# SCH_Decimal_Display_2021-10-08.net
KiCad netlist of a schematic drawn in EasyEDA
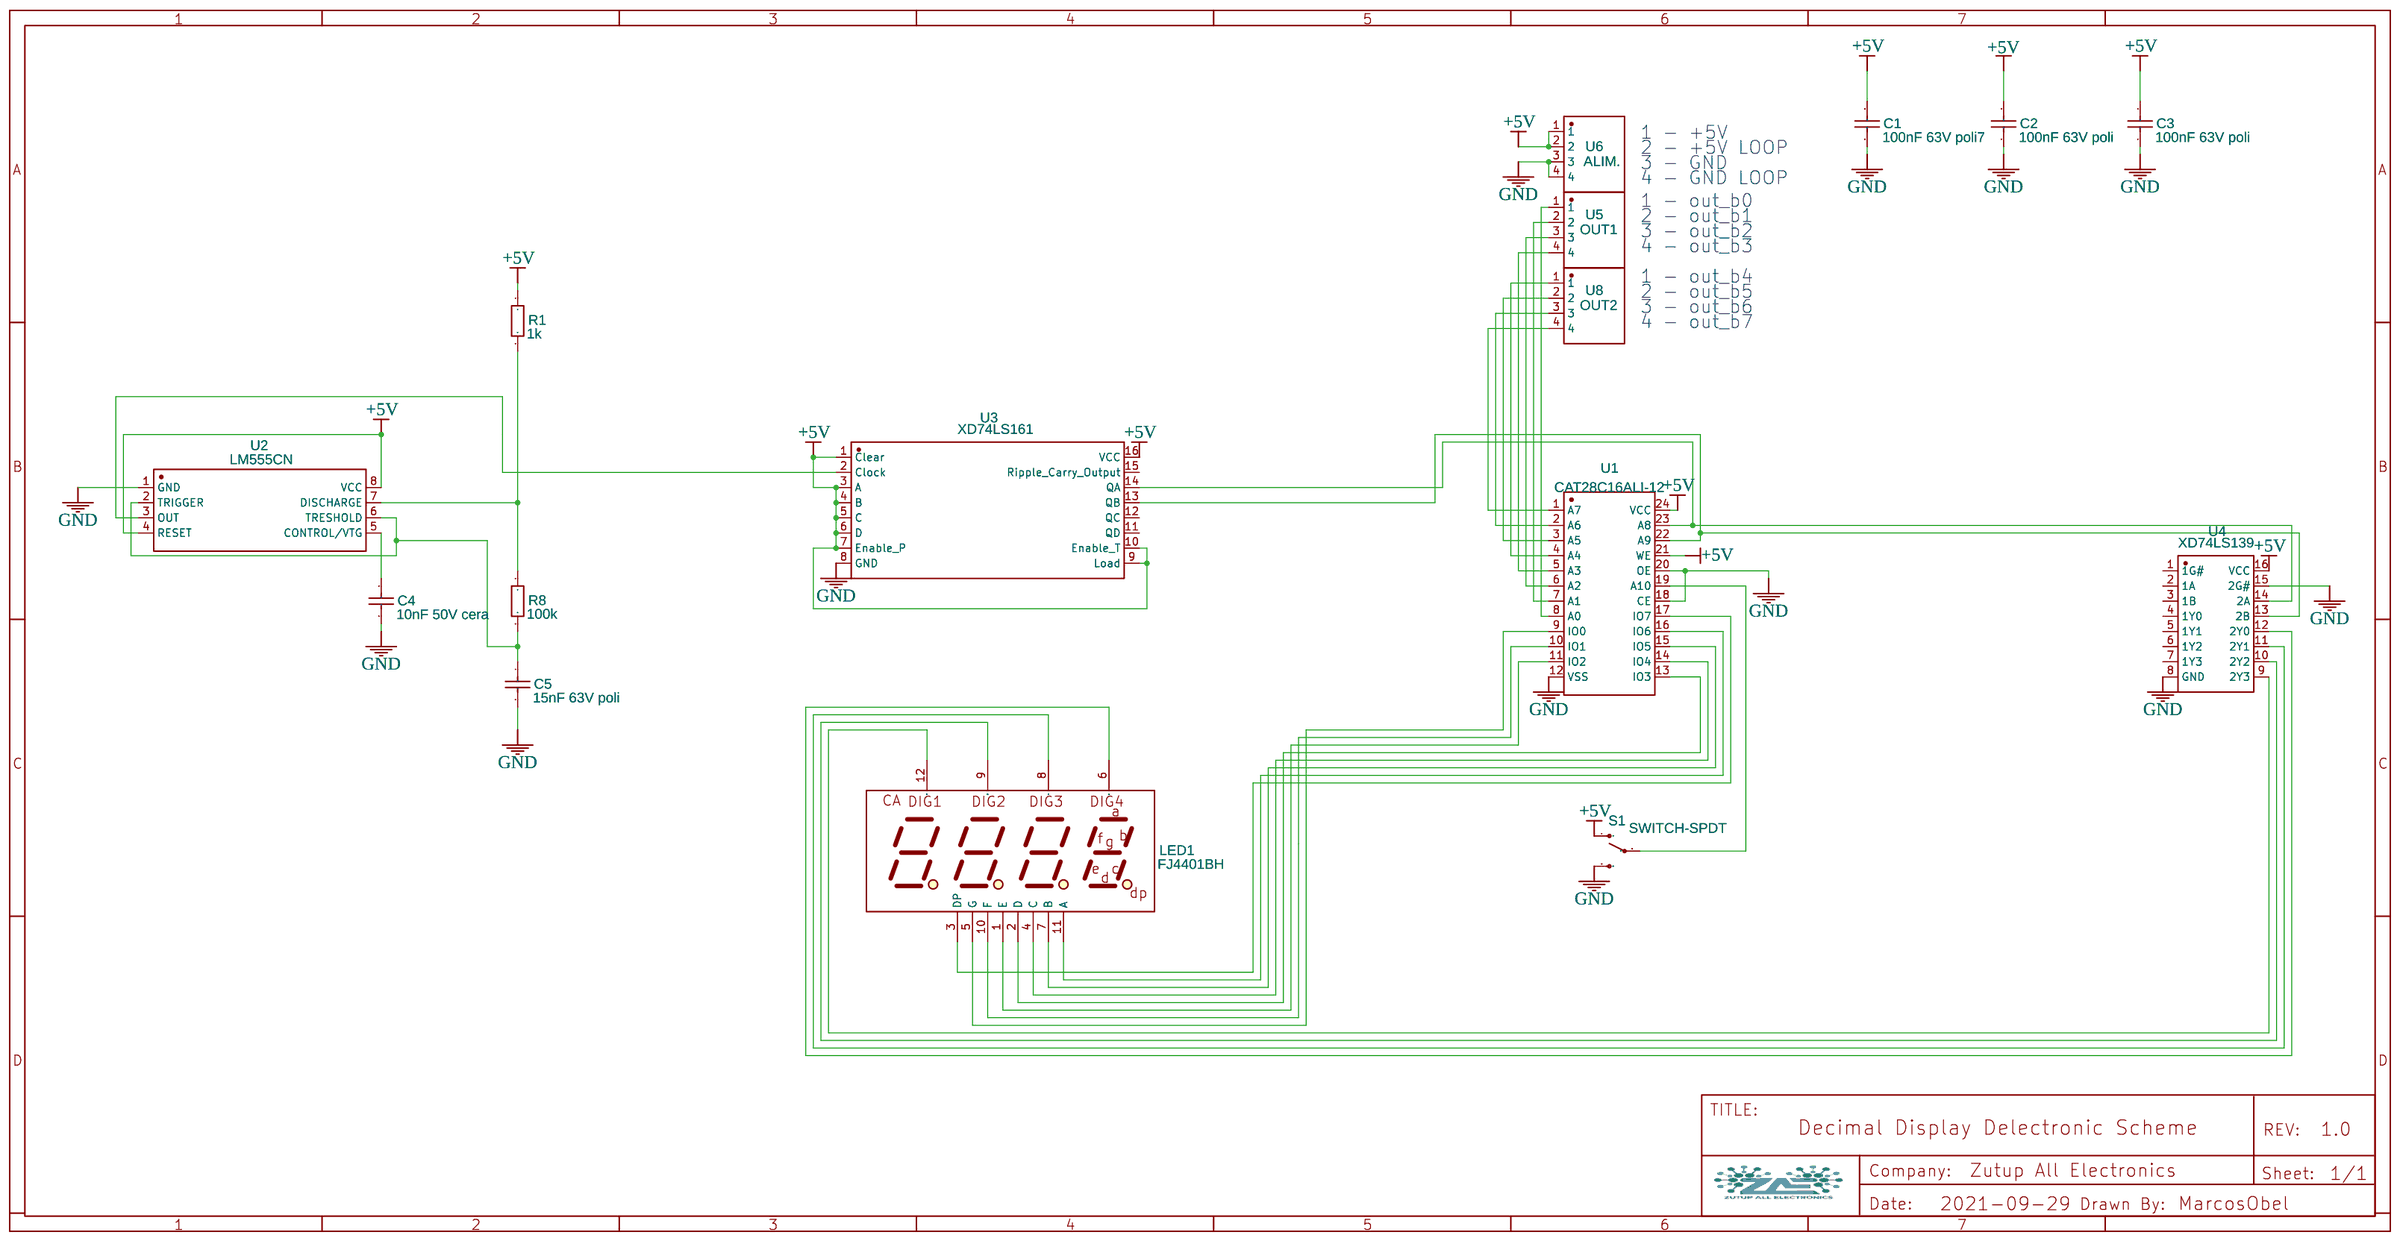
[diagram p0: schematic sheet]

(export (version "E")
  (design (tool "Eeschema 10.0.6"))
  (components
    (comp (ref "C1")
      (value "100nF 63V poli7")
      (fields
        (field (name "BOM_Manufacturer Part") "SR305C105KAR")
        (field (name "BOM_Supplier Part") "C444741")
      )
      (libsource (lib "") (part "SR305C105KAR"))
    )
    (comp (ref "C2")
      (value "100nF 63V poli")
      (fields
        (field (name "BOM_Manufacturer Part") "SR305C105KAR")
        (field (name "BOM_Supplier Part") "C444741")
      )
      (libsource (lib "") (part "SR305C105KAR"))
    )
    (comp (ref "C3")
      (value "100nF 63V poli")
      (fields
        (field (name "BOM_Manufacturer Part") "SR305C105KAR")
        (field (name "BOM_Supplier Part") "C444741")
      )
      (libsource (lib "") (part "SR305C105KAR"))
    )
    (comp (ref "C4")
      (value "10nF 50V cera")
      (fields
        (field (name "BOM_Manufacturer Part") "SR305C105KAR")
        (field (name "BOM_Supplier Part") "C444741")
      )
      (libsource (lib "") (part "SR305C105KAR"))
    )
    (comp (ref "C5")
      (value "15nF 63V poli")
      (fields
        (field (name "BOM_Manufacturer Part") "SR305C105KAR")
        (field (name "BOM_Supplier Part") "C444741")
      )
      (libsource (lib "") (part "SR305C105KAR"))
    )
    (comp (ref "LED1")
      (value "FJ4401BH")
      (fields (field (name "BOM_Supplier Part") "C10712"))
      (libsource (lib "") (part "FJ4401BH"))
    )
    (comp (ref "R1")
      (value "1k")
      (fields
        (field (name "BOM_Manufacturer Part") "CFR02SJ0823A10")
        (field (name "BOM_Supplier Part") "C69876")
      )
      (libsource (lib "") (part "CFR02SJ0823A10"))
    )
    (comp (ref "R8")
      (value "100k")
      (fields
        (field (name "BOM_Manufacturer Part") "CFR02SJ0823A10")
        (field (name "BOM_Supplier Part") "C69876")
      )
      (libsource (lib "") (part "CFR02SJ0823A10"))
    )
    (comp (ref "S1") (value "SWITCH-SPDT") (libsource (lib "") (part "SWITCH-SPDT")))
    (comp (ref "U1") (value "CAT28C16ALI-12") (libsource (lib "") (part "CAT28C16ALI-12")))
    (comp (ref "U2")
      (value "LM555CN")
      (fields (field (name "BOM_Supplier Part") "C110322"))
      (libsource (lib "") (part "LM555CN"))
    )
    (comp (ref "U3")
      (value "XD74LS161")
      (fields (field (name "BOM_Supplier Part") "C609766"))
      (libsource (lib "") (part "XD74LS161"))
    )
    (comp (ref "U4")
      (value "XD74LS139")
      (fields (field (name "BOM_Supplier Part") "C521175"))
      (libsource (lib "") (part "XD74LS139"))
    )
    (comp (ref "U5")
      (value "OUT1")
      (fields (field (name "BOM_Manufacturer Part") "171825-4") (field (name "BOM_Supplier Part") "C210162"))
      (libsource (lib "") (part "171825-4"))
    )
    (comp (ref "U6")
      (value "ALIM.")
      (fields (field (name "BOM_Manufacturer Part") "171825-4") (field (name "BOM_Supplier Part") "C210162"))
      (libsource (lib "") (part "171825-4"))
    )
    (comp (ref "U8")
      (value "OUT2")
      (fields (field (name "BOM_Manufacturer Part") "171825-4") (field (name "BOM_Supplier Part") "C210162"))
      (libsource (lib "") (part "171825-4"))
    )
  )
  (nets
    (net (code "1") (name "+5V") (class "Default")
      (node (ref "C1") (pin "1") (pinfunction "1_1") (pintype "input"))
      (node (ref "C2") (pin "1") (pinfunction "1_1") (pintype "input"))
      (node (ref "C3") (pin "1") (pinfunction "1_1") (pintype "input"))
      (node (ref "R1") (pin "1") (pinfunction "1_1") (pintype "input"))
      (node (ref "S1") (pin "1") (pinfunction "O_1") (pintype "unspecified"))
      (node (ref "U1") (pin "21") (pinfunction "WE_21") (pintype "unspecified"))
      (node (ref "U1") (pin "24") (pinfunction "VCC_24") (pintype "unspecified"))
      (node (ref "U2") (pin "4") (pinfunction "RESET_4") (pintype "unspecified"))
      (node (ref "U2") (pin "8") (pinfunction "VCC_8") (pintype "unspecified"))
      (node (ref "U3") (pin "1") (pinfunction "Clear_1") (pintype "unspecified"))
      (node (ref "U3") (pin "10") (pinfunction "Enable_T_10") (pintype "unspecified"))
      (node (ref "U3") (pin "16") (pinfunction "VCC_16") (pintype "unspecified"))
      (node (ref "U3") (pin "3") (pinfunction "A_3") (pintype "unspecified"))
      (node (ref "U3") (pin "4") (pinfunction "B_4") (pintype "unspecified"))
      (node (ref "U3") (pin "5") (pinfunction "C_5") (pintype "unspecified"))
      (node (ref "U3") (pin "6") (pinfunction "D_6") (pintype "unspecified"))
      (node (ref "U3") (pin "7") (pinfunction "Enable_P_7") (pintype "unspecified"))
      (node (ref "U3") (pin "9") (pinfunction "Load_9") (pintype "unspecified"))
      (node (ref "U4") (pin "16") (pinfunction "VCC_16") (pintype "unspecified"))
      (node (ref "U6") (pin "1") (pinfunction "1_1") (pintype "unspecified"))
      (node (ref "U6") (pin "2") (pinfunction "2_2") (pintype "unspecified"))
    )
    (net (code "2") (name "GND") (class "Default")
      (node (ref "C1") (pin "2") (pinfunction "2_2") (pintype "input"))
      (node (ref "C2") (pin "2") (pinfunction "2_2") (pintype "input"))
      (node (ref "C3") (pin "2") (pinfunction "2_2") (pintype "input"))
      (node (ref "C4") (pin "2") (pinfunction "2_2") (pintype "input"))
      (node (ref "C5") (pin "2") (pinfunction "2_2") (pintype "input"))
      (node (ref "S1") (pin "3") (pinfunction "S_3") (pintype "unspecified"))
      (node (ref "U1") (pin "12") (pinfunction "VSS_12") (pintype "unspecified"))
      (node (ref "U1") (pin "18") (pinfunction "CE_18") (pintype "unspecified"))
      (node (ref "U1") (pin "20") (pinfunction "OE_20") (pintype "unspecified"))
      (node (ref "U2") (pin "1") (pinfunction "GND_1") (pintype "unspecified"))
      (node (ref "U3") (pin "8") (pinfunction "GND_8") (pintype "unspecified"))
      (node (ref "U4") (pin "15") (pinfunction "2G#_15") (pintype "unspecified"))
      (node (ref "U4") (pin "8") (pinfunction "GND_8") (pintype "unspecified"))
      (node (ref "U6") (pin "3") (pinfunction "3_3") (pintype "unspecified"))
      (node (ref "U6") (pin "4") (pinfunction "4_4") (pintype "unspecified"))
    )
    (net (code "3") (name "Net-(LED1-A)") (class "Default")
      (node (ref "LED1") (pin "11") (pinfunction "A_11") (pintype "input"))
      (node (ref "U1") (pin "16") (pinfunction "IO6_16") (pintype "unspecified"))
    )
    (net (code "4") (name "Net-(LED1-B)") (class "Default")
      (node (ref "LED1") (pin "7") (pinfunction "B_7") (pintype "input"))
      (node (ref "U1") (pin "15") (pinfunction "IO5_15") (pintype "unspecified"))
    )
    (net (code "5") (name "Net-(LED1-C)") (class "Default")
      (node (ref "LED1") (pin "4") (pinfunction "C_4") (pintype "input"))
      (node (ref "U1") (pin "14") (pinfunction "IO4_14") (pintype "unspecified"))
    )
    (net (code "6") (name "Net-(LED1-D)") (class "Default")
      (node (ref "LED1") (pin "2") (pinfunction "D_2") (pintype "input"))
      (node (ref "U1") (pin "13") (pinfunction "IO3_13") (pintype "unspecified"))
    )
    (net (code "7") (name "Net-(LED1-DIG1)") (class "Default")
      (node (ref "LED1") (pin "12") (pinfunction "DIG1_12") (pintype "input"))
      (node (ref "U4") (pin "9") (pinfunction "2Y3_9") (pintype "unspecified"))
    )
    (net (code "8") (name "Net-(LED1-DIG2)") (class "Default")
      (node (ref "LED1") (pin "9") (pinfunction "DIG2_9") (pintype "input"))
      (node (ref "U4") (pin "10") (pinfunction "2Y2_10") (pintype "unspecified"))
    )
    (net (code "9") (name "Net-(LED1-DIG3)") (class "Default")
      (node (ref "LED1") (pin "8") (pinfunction "DIG3_8") (pintype "input"))
      (node (ref "U4") (pin "11") (pinfunction "2Y1_11") (pintype "unspecified"))
    )
    (net (code "10") (name "Net-(LED1-DIG4)") (class "Default")
      (node (ref "LED1") (pin "6") (pinfunction "DIG4_6") (pintype "input"))
      (node (ref "U4") (pin "12") (pinfunction "2Y0_12") (pintype "unspecified"))
    )
    (net (code "11") (name "Net-(LED1-DP)") (class "Default")
      (node (ref "LED1") (pin "3") (pinfunction "DP_3") (pintype "input"))
      (node (ref "U1") (pin "17") (pinfunction "IO7_17") (pintype "unspecified"))
    )
    (net (code "12") (name "Net-(LED1-E)") (class "Default")
      (node (ref "LED1") (pin "1") (pinfunction "E_1") (pintype "input"))
      (node (ref "U1") (pin "11") (pinfunction "IO2_11") (pintype "unspecified"))
    )
    (net (code "13") (name "Net-(LED1-F)") (class "Default")
      (node (ref "LED1") (pin "10") (pinfunction "F_10") (pintype "input"))
      (node (ref "U1") (pin "10") (pinfunction "IO1_10") (pintype "unspecified"))
    )
    (net (code "14") (name "Net-(LED1-G)") (class "Default")
      (node (ref "LED1") (pin "5") (pinfunction "G_5") (pintype "input"))
      (node (ref "U1") (pin "9") (pinfunction "IO0_9") (pintype "unspecified"))
    )
    (net (code "15") (name "Net-(S1-P)") (class "Default")
      (node (ref "S1") (pin "2") (pinfunction "P_2") (pintype "unspecified"))
      (node (ref "U1") (pin "19") (pinfunction "A10_19") (pintype "unspecified"))
    )
    (net (code "16") (name "Net-(U1-A0)") (class "Default")
      (node (ref "U1") (pin "8") (pinfunction "A0_8") (pintype "unspecified"))
      (node (ref "U5") (pin "1") (pinfunction "1_1") (pintype "unspecified"))
    )
    (net (code "17") (name "Net-(U1-A1)") (class "Default")
      (node (ref "U1") (pin "7") (pinfunction "A1_7") (pintype "unspecified"))
      (node (ref "U5") (pin "2") (pinfunction "2_2") (pintype "unspecified"))
    )
    (net (code "18") (name "Net-(U1-A2)") (class "Default")
      (node (ref "U1") (pin "6") (pinfunction "A2_6") (pintype "unspecified"))
      (node (ref "U5") (pin "3") (pinfunction "3_3") (pintype "unspecified"))
    )
    (net (code "19") (name "Net-(U1-A3)") (class "Default")
      (node (ref "U1") (pin "5") (pinfunction "A3_5") (pintype "unspecified"))
      (node (ref "U5") (pin "4") (pinfunction "4_4") (pintype "unspecified"))
    )
    (net (code "20") (name "Net-(U1-A4)") (class "Default")
      (node (ref "U1") (pin "4") (pinfunction "A4_4") (pintype "unspecified"))
      (node (ref "U8") (pin "1") (pinfunction "1_1") (pintype "unspecified"))
    )
    (net (code "21") (name "Net-(U1-A5)") (class "Default")
      (node (ref "U1") (pin "3") (pinfunction "A5_3") (pintype "unspecified"))
      (node (ref "U8") (pin "2") (pinfunction "2_2") (pintype "unspecified"))
    )
    (net (code "22") (name "Net-(U1-A6)") (class "Default")
      (node (ref "U1") (pin "2") (pinfunction "A6_2") (pintype "unspecified"))
      (node (ref "U8") (pin "3") (pinfunction "3_3") (pintype "unspecified"))
    )
    (net (code "23") (name "Net-(U1-A7)") (class "Default")
      (node (ref "U1") (pin "1") (pinfunction "A7_1") (pintype "unspecified"))
      (node (ref "U8") (pin "4") (pinfunction "4_4") (pintype "unspecified"))
    )
    (net (code "24") (name "Net-(U1-A8)") (class "Default")
      (node (ref "U1") (pin "23") (pinfunction "A8_23") (pintype "unspecified"))
      (node (ref "U3") (pin "14") (pinfunction "QA_14") (pintype "unspecified"))
      (node (ref "U4") (pin "14") (pinfunction "2A_14") (pintype "unspecified"))
    )
    (net (code "25") (name "Net-(U1-A9)") (class "Default")
      (node (ref "U1") (pin "22") (pinfunction "A9_22") (pintype "unspecified"))
      (node (ref "U3") (pin "13") (pinfunction "QB_13") (pintype "unspecified"))
      (node (ref "U4") (pin "13") (pinfunction "2B_13") (pintype "unspecified"))
    )
    (net (code "26") (name "Net-(U2-CONTROL{slash}VTG)") (class "Default")
      (node (ref "C4") (pin "1") (pinfunction "1_1") (pintype "input"))
      (node (ref "U2") (pin "5") (pinfunction "CONTROL/VTG_5") (pintype "unspecified"))
    )
    (net (code "27") (name "Net-(U2-DISCHARGE)") (class "Default")
      (node (ref "R1") (pin "2") (pinfunction "2_2") (pintype "input"))
      (node (ref "R8") (pin "1") (pinfunction "1_1") (pintype "input"))
      (node (ref "U2") (pin "7") (pinfunction "DISCHARGE_7") (pintype "unspecified"))
    )
    (net (code "28") (name "Net-(U2-OUT)") (class "Default")
      (node (ref "U2") (pin "3") (pinfunction "OUT_3") (pintype "unspecified"))
      (node (ref "U3") (pin "2") (pinfunction "Clock_2") (pintype "unspecified"))
    )
    (net (code "29") (name "Net-(U2-TRESHOLD)") (class "Default")
      (node (ref "C5") (pin "1") (pinfunction "1_1") (pintype "input"))
      (node (ref "R8") (pin "2") (pinfunction "2_2") (pintype "input"))
      (node (ref "U2") (pin "2") (pinfunction "TRIGGER_2") (pintype "unspecified"))
      (node (ref "U2") (pin "6") (pinfunction "TRESHOLD_6") (pintype "unspecified"))
    )
    (net (code "30") (name "unconnected-(U3-QC-Pad12)") (class "Default")
      (node (ref "U3") (pin "12") (pinfunction "QC_12") (pintype "unspecified"))
    )
    (net (code "31") (name "unconnected-(U3-QD-Pad11)") (class "Default")
      (node (ref "U3") (pin "11") (pinfunction "QD_11") (pintype "unspecified"))
    )
    (net (code "32") (name "unconnected-(U3-Ripple_Carry_Output-Pad15)") (class "Default")
      (node (ref "U3") (pin "15") (pinfunction "Ripple_Carry_Output_15") (pintype "unspecified"))
    )
    (net (code "33") (name "unconnected-(U4-1A-Pad2)") (class "Default")
      (node (ref "U4") (pin "2") (pinfunction "1A_2") (pintype "unspecified"))
    )
    (net (code "34") (name "unconnected-(U4-1B-Pad3)") (class "Default")
      (node (ref "U4") (pin "3") (pinfunction "1B_3") (pintype "unspecified"))
    )
    (net (code "35") (name "unconnected-(U4-1G#-Pad1)") (class "Default")
      (node (ref "U4") (pin "1") (pinfunction "1G#_1") (pintype "unspecified"))
    )
    (net (code "36") (name "unconnected-(U4-1Y0-Pad4)") (class "Default")
      (node (ref "U4") (pin "4") (pinfunction "1Y0_4") (pintype "unspecified"))
    )
    (net (code "37") (name "unconnected-(U4-1Y1-Pad5)") (class "Default")
      (node (ref "U4") (pin "5") (pinfunction "1Y1_5") (pintype "unspecified"))
    )
    (net (code "38") (name "unconnected-(U4-1Y2-Pad6)") (class "Default")
      (node (ref "U4") (pin "6") (pinfunction "1Y2_6") (pintype "unspecified"))
    )
    (net (code "39") (name "unconnected-(U4-1Y3-Pad7)") (class "Default")
      (node (ref "U4") (pin "7") (pinfunction "1Y3_7") (pintype "unspecified"))
    )
  )
)
